# SCH_NFC-Buisness-Card_2024-03-13.net
KiCad netlist of a schematic drawn in EasyEDA
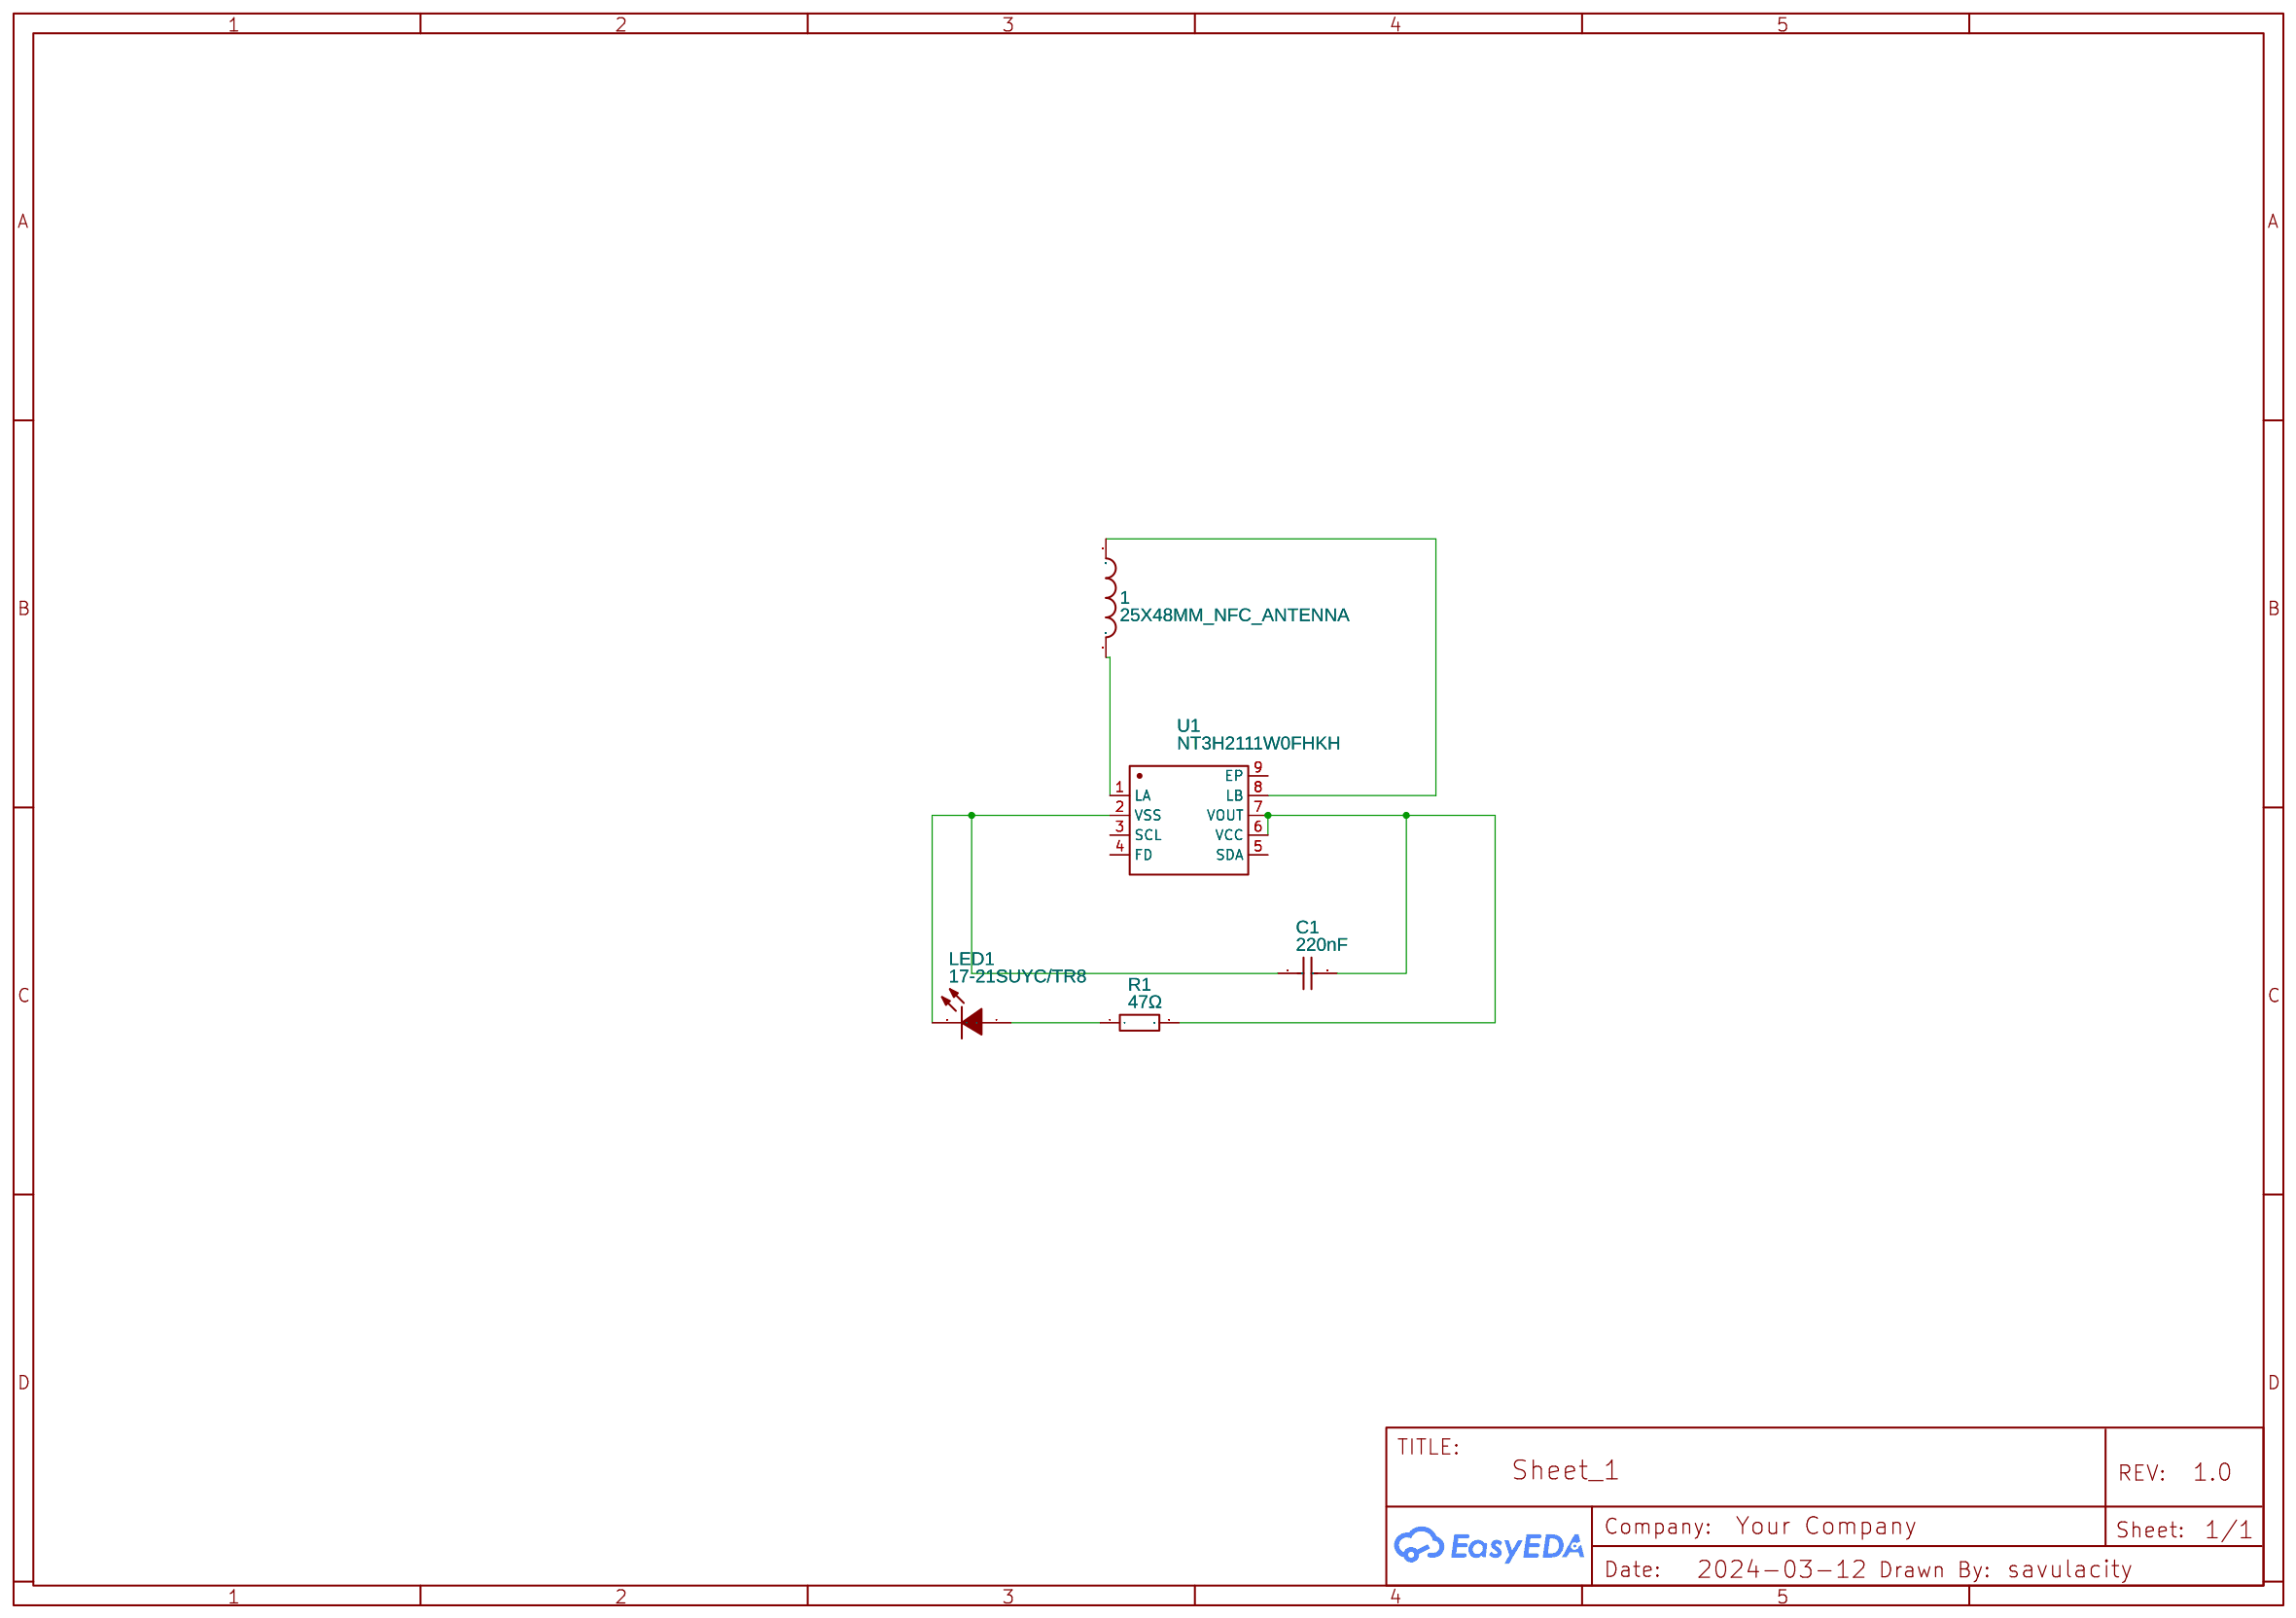
[diagram p0: schematic sheet]

(export (version "E")
  (design (tool "Eeschema 10.0.6"))
  (components
    (comp (ref "1") (value "25X48MM_NFC_ANTENNA") (libsource (lib "") (part "25X48MM_NFC_ANTENNA")))
    (comp (ref "C1")
      (value "220nF")
      (fields
        (field (name "Manufacturer Part") "CL10B224KA8NNNC")
        (field (name "Manufacturer") "SAMSUNG(三星)")
      )
      (libsource (lib "") (part "CL10B224KA8NNNC"))
    )
    (comp (ref "LED1")
      (value "17-21SUYC/TR8")
      (fields (field (name "Manufacturer Part") "KT-0805黄灯") (field (name "Manufacturer") "KENTO"))
      (libsource (lib "") (part "17-21SUYC/TR8"))
    )
    (comp (ref "R1")
      (value "47Ω")
      (fields
        (field (name "Manufacturer Part") "0603WAF470JT5E")
        (field (name "Manufacturer") "UNI-ROYAL(厚声)")
      )
      (libsource (lib "") (part "0603WAF470JT5E"))
    )
    (comp (ref "U1")
      (value "NT3H2111W0FHKH")
      (fields (field (name "Manufacturer") "NXP(恩智浦)"))
      (libsource (lib "") (part "NT3H2111W0FHKH"))
    )
  )
  (nets
    (net (code "1") (name "Net-(LED1-+)") (class "Default")
      (node (ref "LED1") (pin "1") (pinfunction "+_1") (pintype "unspecified"))
      (node (ref "R1") (pin "1") (pinfunction "1_1") (pintype "input"))
    )
    (net (code "2") (name "Net-(LED1--)") (class "Default")
      (node (ref "C1") (pin "1") (pinfunction "1_1") (pintype "input"))
      (node (ref "LED1") (pin "2") (pinfunction "-_2") (pintype "unspecified"))
      (node (ref "U1") (pin "2") (pinfunction "VSS_2") (pintype "unspecified"))
    )
    (net (code "3") (name "Net-(U1-LA)") (class "Default")
      (node (ref "1") (pin "P$2") (pinfunction "P$2_P$2") (pintype "bidirectional"))
      (node (ref "U1") (pin "1") (pinfunction "LA_1") (pintype "unspecified"))
    )
    (net (code "4") (name "Net-(U1-LB)") (class "Default")
      (node (ref "1") (pin "P$1") (pinfunction "P$1_P$1") (pintype "bidirectional"))
      (node (ref "U1") (pin "8") (pinfunction "LB_8") (pintype "unspecified"))
    )
    (net (code "5") (name "Net-(U1-VCC)") (class "Default")
      (node (ref "C1") (pin "2") (pinfunction "2_2") (pintype "input"))
      (node (ref "R1") (pin "2") (pinfunction "2_2") (pintype "input"))
      (node (ref "U1") (pin "6") (pinfunction "VCC_6") (pintype "unspecified"))
      (node (ref "U1") (pin "7") (pinfunction "VOUT_7") (pintype "unspecified"))
    )
    (net (code "6") (name "unconnected-(U1-EP-Pad9)") (class "Default")
      (node (ref "U1") (pin "9") (pinfunction "EP_9") (pintype "unspecified"))
    )
    (net (code "7") (name "unconnected-(U1-FD-Pad4)") (class "Default")
      (node (ref "U1") (pin "4") (pinfunction "FD_4") (pintype "unspecified"))
    )
    (net (code "8") (name "unconnected-(U1-SCL-Pad3)") (class "Default")
      (node (ref "U1") (pin "3") (pinfunction "SCL_3") (pintype "unspecified"))
    )
    (net (code "9") (name "unconnected-(U1-SDA-Pad5)") (class "Default")
      (node (ref "U1") (pin "5") (pinfunction "SDA_5") (pintype "unspecified"))
    )
  )
)
